# schematic.net
KiCad netlist of a schematic drawn in Altium Designer
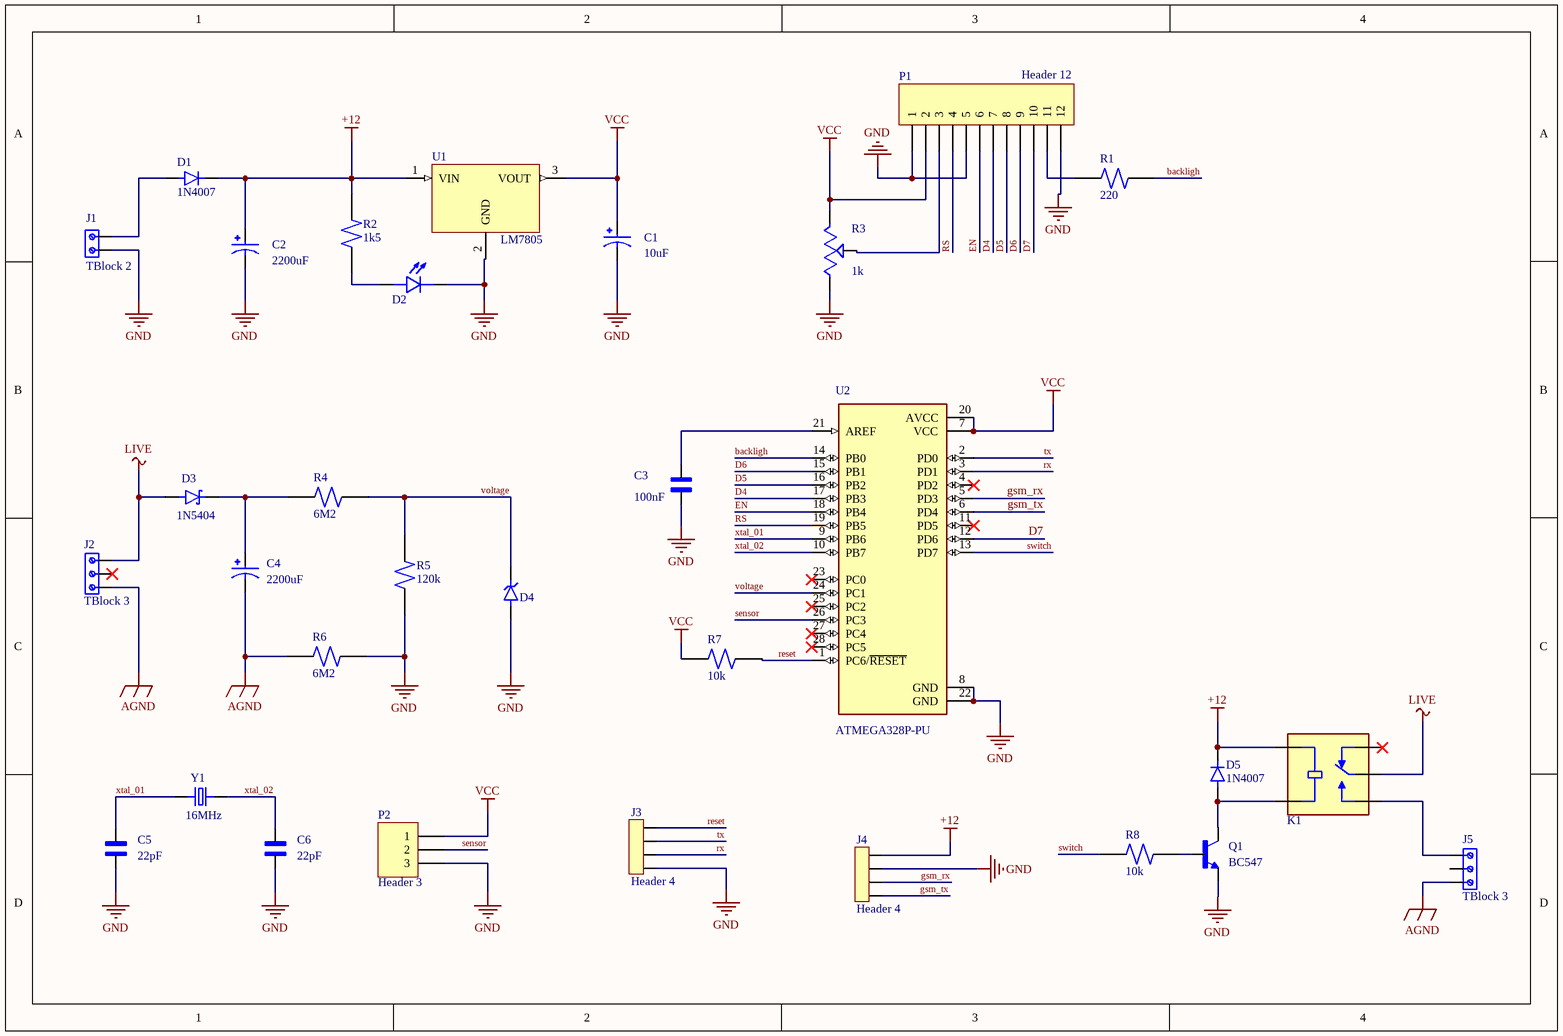
[diagram p0: schematic.SchDoc]

(export (version "E")
  (design (tool "Eeschema 10.0.6"))
  (components
    (comp (ref "C1")
      (value "10uF")
      (footprint "CAPPRD500W50D500H1100")
      (description "FS-A")
      (fields (field (name "MF") "{'manufacturer': u'Panasonic'}") (field (name "MP") "EEUFS0J221B"))
      (libsource (lib "") (part "Electrolytic capacitor_1"))
    )
    (comp (ref "C2")
      (value "2200uF")
      (footprint "CAPPRD500W50D500H1100")
      (description "FS-A")
      (fields (field (name "MF") "{'manufacturer': u'Panasonic'}") (field (name "MP") "EEUFS0J221B"))
      (libsource (lib "Installed library") (part "Electrolytic capacitor"))
    )
    (comp (ref "C3")
      (value "100nF")
      (footprint "CAPRB500W50L450T300H550")
      (description "2200 pF Â±10% 250V Ceramic Capacitor X7R Radial")
      (fields (field (name "DIGI-KEY_PART_NUMBER") "445-173386-1-ND") (field (name "MF") "TDK"))
      (libsource (lib "Installed library") (part "Ceramic capacitor"))
    )
    (comp (ref "C4")
      (value "2200uF")
      (footprint "CAPPRD750W80D1600H2500")
      (fields (field (name "MF") "Panasonic") (field (name "MP") "ECA2GM330"))
      (libsource (lib "Installed library") (part "Capacitor (16 x 25mm)"))
    )
    (comp (ref "C5")
      (value "22pF")
      (footprint "CAPRB500W50L450T300H550")
      (description "2200 pF Â±10% 250V Ceramic Capacitor X7R Radial")
      (fields (field (name "DIGI-KEY_PART_NUMBER") "445-173386-1-ND") (field (name "MF") "TDK"))
      (libsource (lib "Installed library") (part "Ceramic capacitor"))
    )
    (comp (ref "C6")
      (value "22pF")
      (footprint "CAPRB500W50L450T300H550")
      (description "2200 pF Â±10% 250V Ceramic Capacitor X7R Radial")
      (fields (field (name "DIGI-KEY_PART_NUMBER") "445-173386-1-ND") (field (name "MF") "TDK"))
      (libsource (lib "Installed library") (part "Ceramic capacitor"))
    )
    (comp (ref "D1")
      (value "1N4007")
      (footprint "DIOAD1060W80L520D270")
      (description "Diode Switching 1KV 1A 2-Pin DO-41")
      (libsource (lib "Components") (part "1N4007"))
    )
    (comp (ref "D2")
      (value "L08R5000Q1")
      (footprint "LEDRD254W57D500H1070")
      (description "LED, Orange, Through Hole, T-1 3/4 (5mm), 30 mA, 2.1 V, 635 nm")
      (fields (field (name "MF") "{'manufacturer': u'LED Technology'}"))
      (libsource (lib "Installed library") (part "LED"))
    )
    (comp (ref "D3")
      (value "1N5404")
      (footprint "DIOAD1990W125L900D530")
      (description "Diode Standard 400 V 3A Through Hole DO-201AD")
      (fields (field (name "MF") "ON Semiconductor"))
      (libsource (lib "Installed library") (part "Schrotic diode"))
    )
    (comp (ref "D4")
      (value "1N4745A")
      (footprint "DIOAD1060W70L435D230")
      (description "Zener Diode 16V 1W Â±5% Through Hole DO-204AL (DO-41)")
      (fields (field (name "MF") "ON Semiconductor"))
      (libsource (lib "Installed library") (part "Zenner diode"))
    )
    (comp (ref "D5")
      (value "1N4007")
      (footprint "DIOAD1060W80L520D270")
      (description "Diode Switching 1KV 1A 2-Pin DO-41")
      (libsource (lib "Components") (part "1N4007"))
    )
    (comp (ref "J1")
      (value "TBlock 2")
      (footprint "691111710002")
      (description "2 Position Wire to Board Terminal Block Horizontal with Board 0.197 _5.00mm_ Through Hole")
      (fields (field (name "MP") "691111710002") (field (name "MF") "Wurth Electronics"))
      (libsource (lib "Installed library") (part "Terminal Block - 2Pins"))
    )
    (comp (ref "J2")
      (value "TBlock 3")
      (footprint "691214110003")
      (description "3 Position Wire to Board Terminal Block Horizontal with Board 0.138 (3.50mm) Through Hole")
      (fields (field (name "MF") "Wurth Elektronik") (field (name "MP") "691214110003"))
      (libsource (lib "Installed library") (part "Terminal blocks - 3Pins (Small)"))
    )
    (comp (ref "J3")
      (value "Header 4")
      (footprint "SULLINS_PPTC041LFBN-RC")
      (description "4 Position Header Connector Through Hole")
      (fields (field (name "MP") "PPTC041LFBN-RC") (field (name "MF") "Sullins Connector"))
      (libsource (lib "Installed library") (part "Female header - 4Pins"))
    )
    (comp (ref "J4")
      (value "Header 4")
      (footprint "SULLINS_PPTC041LFBN-RC")
      (description "4 Position Header Connector Through Hole")
      (fields (field (name "MP") "PPTC041LFBN-RC") (field (name "MF") "Sullins Connector"))
      (libsource (lib "Installed library") (part "Female header - 4Pins"))
    )
    (comp (ref "J5")
      (value "TBlock 3")
      (footprint "691214110003")
      (description "3 Position Wire to Board Terminal Block Horizontal with Board 0.138 (3.50mm) Through Hole")
      (fields (field (name "MF") "Wurth Elektronik") (field (name "MP") "691214110003"))
      (libsource (lib "Installed library") (part "Terminal blocks - 3Pins (Small)"))
    )
    (comp (ref "K1")
      (value "JQC-3F-1C-24VDC")
      (footprint "RELAY_JQC-3F-1C-24VDC")
      (description "Miniature PCB Relay 24VDC, 10A 250VAC, 15A 125VAC, 10A 250VAC")
      (libsource (lib "Installed library") (part "Relay (Standard)"))
    )
    (comp (ref "P1")
      (value "Header 12")
      (footprint "HDR1X12")
      (description "Header, 12-Pin")
      (fields (field (name "PUBLISHER") "Altium Limited"))
      (libsource (lib "Miscellaneous Connectors") (part "Header 12"))
    )
    (comp (ref "P2")
      (value "Header 3")
      (footprint "HDR1X3")
      (description "Header, 3-Pin")
      (fields (field (name "PUBLISHER") "Altium Limited"))
      (libsource (lib "Miscellaneous Connectors") (part "Header 3"))
    )
    (comp (ref "Q1")
      (value "BC547")
      (footprint "TO92250P510H770-3")
      (fields (field (name "MP") "BC547B"))
      (libsource (lib "Installed library") (part "BC547B"))
    )
    (comp (ref "R1")
      (value "220")
      (footprint "RESAD1100W55L680D260")
      (description "(MFR-25FBF52-10K) 10,2 kOhm bei 1% 0,25W, 1/4W Durchbohrlochwiderstand Axial Metal Film")
      (fields (field (name "DIGI-KEY_PART_NUMBER") "10.2KXBK-ND") (field (name "MF") "Yageo"))
      (libsource (lib "Installed library") (part "Resistor (0.25W)"))
    )
    (comp (ref "R2")
      (value "1k5")
      (footprint "RESAD1100W55L680D260")
      (description "(MFR-25FBF52-10K) 10,2 kOhm bei 1% 0,25W, 1/4W Durchbohrlochwiderstand Axial Metal Film")
      (fields (field (name "DIGI-KEY_PART_NUMBER") "10.2KXBK-ND") (field (name "MF") "Yageo"))
      (libsource (lib "Installed library") (part "Resistor (0.25W)"))
    )
    (comp (ref "R3")
      (value "1k")
      (footprint "TRIM_3306F-1-105")
      (fields (field (name "MF") "Bourns") (field (name "MP") "3306F-1-105"))
      (libsource (lib "Installed library") (part "Potentiometer1"))
    )
    (comp (ref "R4")
      (value "6M2")
      (footprint "RESAD1100W55L680D260")
      (description "(MFR-25FBF52-10K) 10,2 kOhm bei 1% 0,25W, 1/4W Durchbohrlochwiderstand Axial Metal Film")
      (fields (field (name "DIGI-KEY_PART_NUMBER") "10.2KXBK-ND") (field (name "MF") "Yageo"))
      (libsource (lib "Installed library") (part "Resistor (0.25W)"))
    )
    (comp (ref "R5")
      (value "120k")
      (footprint "RESAD1100W55L680D260")
      (description "(MFR-25FBF52-10K) 10,2 kOhm bei 1% 0,25W, 1/4W Durchbohrlochwiderstand Axial Metal Film")
      (fields (field (name "DIGI-KEY_PART_NUMBER") "10.2KXBK-ND") (field (name "MF") "Yageo"))
      (libsource (lib "Installed library") (part "Resistor (0.25W)"))
    )
    (comp (ref "R6")
      (value "6M2")
      (footprint "RESAD1100W55L680D260")
      (description "(MFR-25FBF52-10K) 10,2 kOhm bei 1% 0,25W, 1/4W Durchbohrlochwiderstand Axial Metal Film")
      (fields (field (name "DIGI-KEY_PART_NUMBER") "10.2KXBK-ND") (field (name "MF") "Yageo"))
      (libsource (lib "Installed library") (part "Resistor (0.25W)"))
    )
    (comp (ref "R7")
      (value "10k")
      (footprint "RESAD1100W55L680D260")
      (description "(MFR-25FBF52-10K) 10,2 kOhm bei 1% 0,25W, 1/4W Durchbohrlochwiderstand Axial Metal Film")
      (fields (field (name "DIGI-KEY_PART_NUMBER") "10.2KXBK-ND") (field (name "MF") "Yageo"))
      (libsource (lib "Installed library") (part "Resistor (0.25W)"))
    )
    (comp (ref "R8")
      (value "10k")
      (footprint "RESAD1100W55L680D260")
      (description "(MFR-25FBF52-10K) 10,2 kOhm bei 1% 0,25W, 1/4W Durchbohrlochwiderstand Axial Metal Film")
      (fields (field (name "DIGI-KEY_PART_NUMBER") "10.2KXBK-ND") (field (name "MF") "Yageo"))
      (libsource (lib "Installed library") (part "Resistor (0.25W)"))
    )
    (comp (ref "U1")
      (value "LM7805")
      (footprint "TO255P1020X450X1968-3")
      (fields (field (name "MP") "LM7805CT/NOPB"))
      (libsource (lib "Voltage regulator") (part "LM78__"))
    )
    (comp (ref "U2")
      (value "ATMEGA328P-PU")
      (footprint "DIP794W46P254L2967H457Q28B")
      (description "ATmega Series 20 MHz 32 KB Flash 2 KB SRAM 8-Bit Microcontroller - DIP-28")
      (libsource (lib "Installed library") (part "ATMEGA328P-PU"))
    )
    (comp (ref "Y1")
      (value "16MHz")
      (footprint "XTAL_ECS-160-20-4X")
      (description "CRYSTAL T/H")
      (fields (field (name "MF") "{'manufacturer': u'ECS Inc.'}") (field (name "MP") "ECS-160-S-4"))
      (libsource (lib "Installed library") (part "Crystal oscilator"))
    )
  )
  (nets
    (net (code "1") (name "+12") (class "Default")
      (node (ref "C2") (pin "P") (pinfunction "P_P") (pintype "passive"))
      (node (ref "D1") (pin "C") (pinfunction "C_C") (pintype "passive"))
      (node (ref "D5") (pin "C") (pinfunction "C_C") (pintype "passive"))
      (node (ref "J4") (pin "1") (pinfunction "1_1") (pintype "passive"))
      (node (ref "K1") (pin "COIL1") (pinfunction "COIL1_COIL1") (pintype "passive"))
      (node (ref "R2") (pin "2") (pinfunction "2_2") (pintype "passive"))
      (node (ref "U1") (pin "1") (pinfunction "VIN_1") (pintype "input"))
    )
    (net (code "2") (name "/D4") (class "Default")
      (node (ref "P1") (pin "7") (pinfunction "7_7") (pintype "passive"))
      (node (ref "U2") (pin "17") (pinfunction "PB3_17") (pintype "bidirectional"))
    )
    (net (code "3") (name "/D5") (class "Default")
      (node (ref "P1") (pin "8") (pinfunction "8_8") (pintype "passive"))
      (node (ref "U2") (pin "16") (pinfunction "PB2_16") (pintype "bidirectional"))
    )
    (net (code "4") (name "/D6") (class "Default")
      (node (ref "P1") (pin "9") (pinfunction "9_9") (pintype "passive"))
      (node (ref "U2") (pin "15") (pinfunction "PB1_15") (pintype "bidirectional"))
    )
    (net (code "5") (name "/D7") (class "Default")
      (node (ref "P1") (pin "10") (pinfunction "10_10") (pintype "passive"))
      (node (ref "U2") (pin "12") (pinfunction "PD6_12") (pintype "bidirectional"))
    )
    (net (code "6") (name "/EN") (class "Default")
      (node (ref "P1") (pin "6") (pinfunction "6_6") (pintype "passive"))
      (node (ref "U2") (pin "18") (pinfunction "PB4_18") (pintype "bidirectional"))
    )
    (net (code "7") (name "/RS") (class "Default")
      (node (ref "P1") (pin "4") (pinfunction "4_4") (pintype "passive"))
      (node (ref "U2") (pin "19") (pinfunction "PB5_19") (pintype "bidirectional"))
    )
    (net (code "8") (name "/backligh") (class "Default")
      (node (ref "R1") (pin "1") (pinfunction "1_1") (pintype "passive"))
      (node (ref "U2") (pin "14") (pinfunction "PB0_14") (pintype "bidirectional"))
    )
    (net (code "9") (name "/gsm_rx") (class "Default")
      (node (ref "J4") (pin "3") (pinfunction "3_3") (pintype "passive"))
      (node (ref "U2") (pin "5") (pinfunction "PD3_5") (pintype "bidirectional"))
    )
    (net (code "10") (name "/gsm_tx") (class "Default")
      (node (ref "J4") (pin "4") (pinfunction "4_4") (pintype "passive"))
      (node (ref "U2") (pin "6") (pinfunction "PD4_6") (pintype "bidirectional"))
    )
    (net (code "11") (name "/reset") (class "Default")
      (node (ref "J3") (pin "1") (pinfunction "1_1") (pintype "passive"))
      (node (ref "R7") (pin "1") (pinfunction "1_1") (pintype "passive"))
      (node (ref "U2") (pin "1") (pinfunction "PC6/~{RESET}_1") (pintype "bidirectional"))
    )
    (net (code "12") (name "/rx") (class "Default")
      (node (ref "J3") (pin "3") (pinfunction "3_3") (pintype "passive"))
      (node (ref "U2") (pin "3") (pinfunction "PD1_3") (pintype "bidirectional"))
    )
    (net (code "13") (name "/sensor") (class "Default")
      (node (ref "P2") (pin "2") (pinfunction "2_2") (pintype "passive"))
      (node (ref "U2") (pin "26") (pinfunction "PC3_26") (pintype "bidirectional"))
    )
    (net (code "14") (name "/switch") (class "Default")
      (node (ref "R8") (pin "2") (pinfunction "2_2") (pintype "passive"))
      (node (ref "U2") (pin "13") (pinfunction "PD7_13") (pintype "bidirectional"))
    )
    (net (code "15") (name "/tx") (class "Default")
      (node (ref "J3") (pin "2") (pinfunction "2_2") (pintype "passive"))
      (node (ref "U2") (pin "2") (pinfunction "PD0_2") (pintype "bidirectional"))
    )
    (net (code "16") (name "/voltage") (class "Default")
      (node (ref "D4") (pin "C") (pinfunction "K_C") (pintype "passive"))
      (node (ref "R4") (pin "1") (pinfunction "1_1") (pintype "passive"))
      (node (ref "R5") (pin "2") (pinfunction "2_2") (pintype "passive"))
      (node (ref "U2") (pin "24") (pinfunction "PC1_24") (pintype "bidirectional"))
    )
    (net (code "17") (name "/xtal_01") (class "Default")
      (node (ref "C5") (pin "2") (pinfunction "2_2") (pintype "passive"))
      (node (ref "U2") (pin "9") (pinfunction "PB6_9") (pintype "bidirectional"))
      (node (ref "Y1") (pin "1") (pinfunction "1_1") (pintype "passive"))
    )
    (net (code "18") (name "/xtal_02") (class "Default")
      (node (ref "C6") (pin "2") (pinfunction "2_2") (pintype "passive"))
      (node (ref "U2") (pin "10") (pinfunction "PB7_10") (pintype "bidirectional"))
      (node (ref "Y1") (pin "2") (pinfunction "2_2") (pintype "passive"))
    )
    (net (code "19") (name "AGND") (class "Default")
      (node (ref "C4") (pin "N") (pinfunction "N_N") (pintype "passive"))
      (node (ref "J2") (pin "1") (pinfunction "1_1") (pintype "passive"))
      (node (ref "J5") (pin "3") (pinfunction "3_3") (pintype "passive"))
      (node (ref "R6") (pin "2") (pinfunction "2_2") (pintype "passive"))
    )
    (net (code "20") (name "GND") (class "Default")
      (node (ref "C1") (pin "N") (pinfunction "N_N") (pintype "passive"))
      (node (ref "C2") (pin "N") (pinfunction "N_N") (pintype "passive"))
      (node (ref "C3") (pin "1") (pinfunction "1_1") (pintype "passive"))
      (node (ref "C5") (pin "1") (pinfunction "1_1") (pintype "passive"))
      (node (ref "C6") (pin "1") (pinfunction "1_1") (pintype "passive"))
      (node (ref "D2") (pin "C") (pinfunction "C_C") (pintype "passive"))
      (node (ref "D4") (pin "A") (pinfunction "A_A") (pintype "passive"))
      (node (ref "J1") (pin "1") (pinfunction "1_1") (pintype "passive"))
      (node (ref "J3") (pin "4") (pinfunction "4_4") (pintype "passive"))
      (node (ref "J4") (pin "2") (pinfunction "2_2") (pintype "passive"))
      (node (ref "P1") (pin "1") (pinfunction "1_1") (pintype "passive"))
      (node (ref "P1") (pin "12") (pinfunction "12_12") (pintype "passive"))
      (node (ref "P1") (pin "5") (pinfunction "5_5") (pintype "passive"))
      (node (ref "P2") (pin "3") (pinfunction "3_3") (pintype "passive"))
      (node (ref "Q1") (pin "3") (pinfunction "E_3") (pintype "passive"))
      (node (ref "R3") (pin "1") (pinfunction "CCW_1") (pintype "passive"))
      (node (ref "R5") (pin "1") (pinfunction "1_1") (pintype "passive"))
      (node (ref "R6") (pin "1") (pinfunction "1_1") (pintype "passive"))
      (node (ref "U1") (pin "2") (pinfunction "GND_2") (pintype "passive"))
      (node (ref "U2") (pin "22") (pinfunction "GND_22") (pintype "power_in"))
      (node (ref "U2") (pin "8") (pinfunction "GND_8") (pintype "power_in"))
    )
    (net (code "21") (name "LIVE") (class "Default")
      (node (ref "D3") (pin "A") (pinfunction "A_A") (pintype "passive"))
      (node (ref "J2") (pin "3") (pinfunction "3_3") (pintype "passive"))
      (node (ref "K1") (pin "COM") (pinfunction "COM_COM") (pintype "passive"))
    )
    (net (code "22") (name "Net-(D1-PadA)") (class "Default")
      (node (ref "D1") (pin "A") (pinfunction "A_A") (pintype "passive"))
      (node (ref "J1") (pin "2") (pinfunction "2_2") (pintype "passive"))
    )
    (net (code "23") (name "Net-(D2-PadA)") (class "Default")
      (node (ref "D2") (pin "A") (pinfunction "A_A") (pintype "passive"))
      (node (ref "R2") (pin "1") (pinfunction "1_1") (pintype "passive"))
    )
    (net (code "24") (name "Net-(D3-K)") (class "Default")
      (node (ref "C4") (pin "P") (pinfunction "P_P") (pintype "passive"))
      (node (ref "D3") (pin "C") (pinfunction "K_C") (pintype "passive"))
      (node (ref "R4") (pin "2") (pinfunction "2_2") (pintype "passive"))
    )
    (net (code "25") (name "Net-(J5-Pad1)") (class "Default")
      (node (ref "J5") (pin "1") (pinfunction "1_1") (pintype "passive"))
      (node (ref "K1") (pin "NO") (pinfunction "NO_NO") (pintype "passive"))
    )
    (net (code "26") (name "Net-(P1-Pad11)") (class "Default")
      (node (ref "P1") (pin "11") (pinfunction "11_11") (pintype "passive"))
      (node (ref "R1") (pin "2") (pinfunction "2_2") (pintype "passive"))
    )
    (net (code "27") (name "Net-(Q1-B)") (class "Default")
      (node (ref "Q1") (pin "2") (pinfunction "B_2") (pintype "passive"))
      (node (ref "R8") (pin "1") (pinfunction "1_1") (pintype "passive"))
    )
    (net (code "28") (name "Net-(Q1-C)") (class "Default")
      (node (ref "D5") (pin "A") (pinfunction "A_A") (pintype "passive"))
      (node (ref "K1") (pin "COIL2") (pinfunction "COIL2_COIL2") (pintype "passive"))
      (node (ref "Q1") (pin "1") (pinfunction "C_1") (pintype "passive"))
    )
    (net (code "29") (name "Net-(R3-WIPER)") (class "Default")
      (node (ref "P1") (pin "3") (pinfunction "3_3") (pintype "passive"))
      (node (ref "R3") (pin "2") (pinfunction "WIPER_2") (pintype "passive"))
    )
    (net (code "30") (name "Net-(U2-AREF)") (class "Default")
      (node (ref "C3") (pin "2") (pinfunction "2_2") (pintype "passive"))
      (node (ref "U2") (pin "21") (pinfunction "AREF_21") (pintype "input"))
    )
    (net (code "31") (name "VCC") (class "Default")
      (node (ref "C1") (pin "P") (pinfunction "P_P") (pintype "passive"))
      (node (ref "P1") (pin "2") (pinfunction "2_2") (pintype "passive"))
      (node (ref "P2") (pin "1") (pinfunction "1_1") (pintype "passive"))
      (node (ref "R3") (pin "3") (pinfunction "CW_3") (pintype "passive"))
      (node (ref "R7") (pin "2") (pinfunction "2_2") (pintype "passive"))
      (node (ref "U1") (pin "3") (pinfunction "VOUT_3") (pintype "output"))
      (node (ref "U2") (pin "20") (pinfunction "AVCC_20") (pintype "power_in"))
      (node (ref "U2") (pin "7") (pinfunction "VCC_7") (pintype "power_in"))
    )
    (net (code "32") (name "unconnected-(J2-Pad2)") (class "Default")
      (node (ref "J2") (pin "2") (pinfunction "2_2") (pintype "passive+no_connect"))
    )
    (net (code "33") (name "unconnected-(J5-Pad2)") (class "Default")
      (node (ref "J5") (pin "2") (pinfunction "2_2") (pintype "passive"))
    )
    (net (code "34") (name "unconnected-(K1-PadNC)") (class "Default")
      (node (ref "K1") (pin "NC") (pinfunction "NC_NC") (pintype "passive+no_connect"))
    )
    (net (code "35") (name "unconnected-(U2-PC0-Pad23)") (class "Default")
      (node (ref "U2") (pin "23") (pinfunction "PC0_23") (pintype "bidirectional+no_connect"))
    )
    (net (code "36") (name "unconnected-(U2-PC2-Pad25)") (class "Default")
      (node (ref "U2") (pin "25") (pinfunction "PC2_25") (pintype "bidirectional+no_connect"))
    )
    (net (code "37") (name "unconnected-(U2-PC4-Pad27)") (class "Default")
      (node (ref "U2") (pin "27") (pinfunction "PC4_27") (pintype "bidirectional+no_connect"))
    )
    (net (code "38") (name "unconnected-(U2-PC5-Pad28)") (class "Default")
      (node (ref "U2") (pin "28") (pinfunction "PC5_28") (pintype "bidirectional+no_connect"))
    )
    (net (code "39") (name "unconnected-(U2-PD2-Pad4)") (class "Default")
      (node (ref "U2") (pin "4") (pinfunction "PD2_4") (pintype "bidirectional+no_connect"))
    )
    (net (code "40") (name "unconnected-(U2-PD5-Pad11)") (class "Default")
      (node (ref "U2") (pin "11") (pinfunction "PD5_11") (pintype "bidirectional+no_connect"))
    )
  )
)
